# Main.net
KiCad netlist of a schematic drawn in Altium Designer
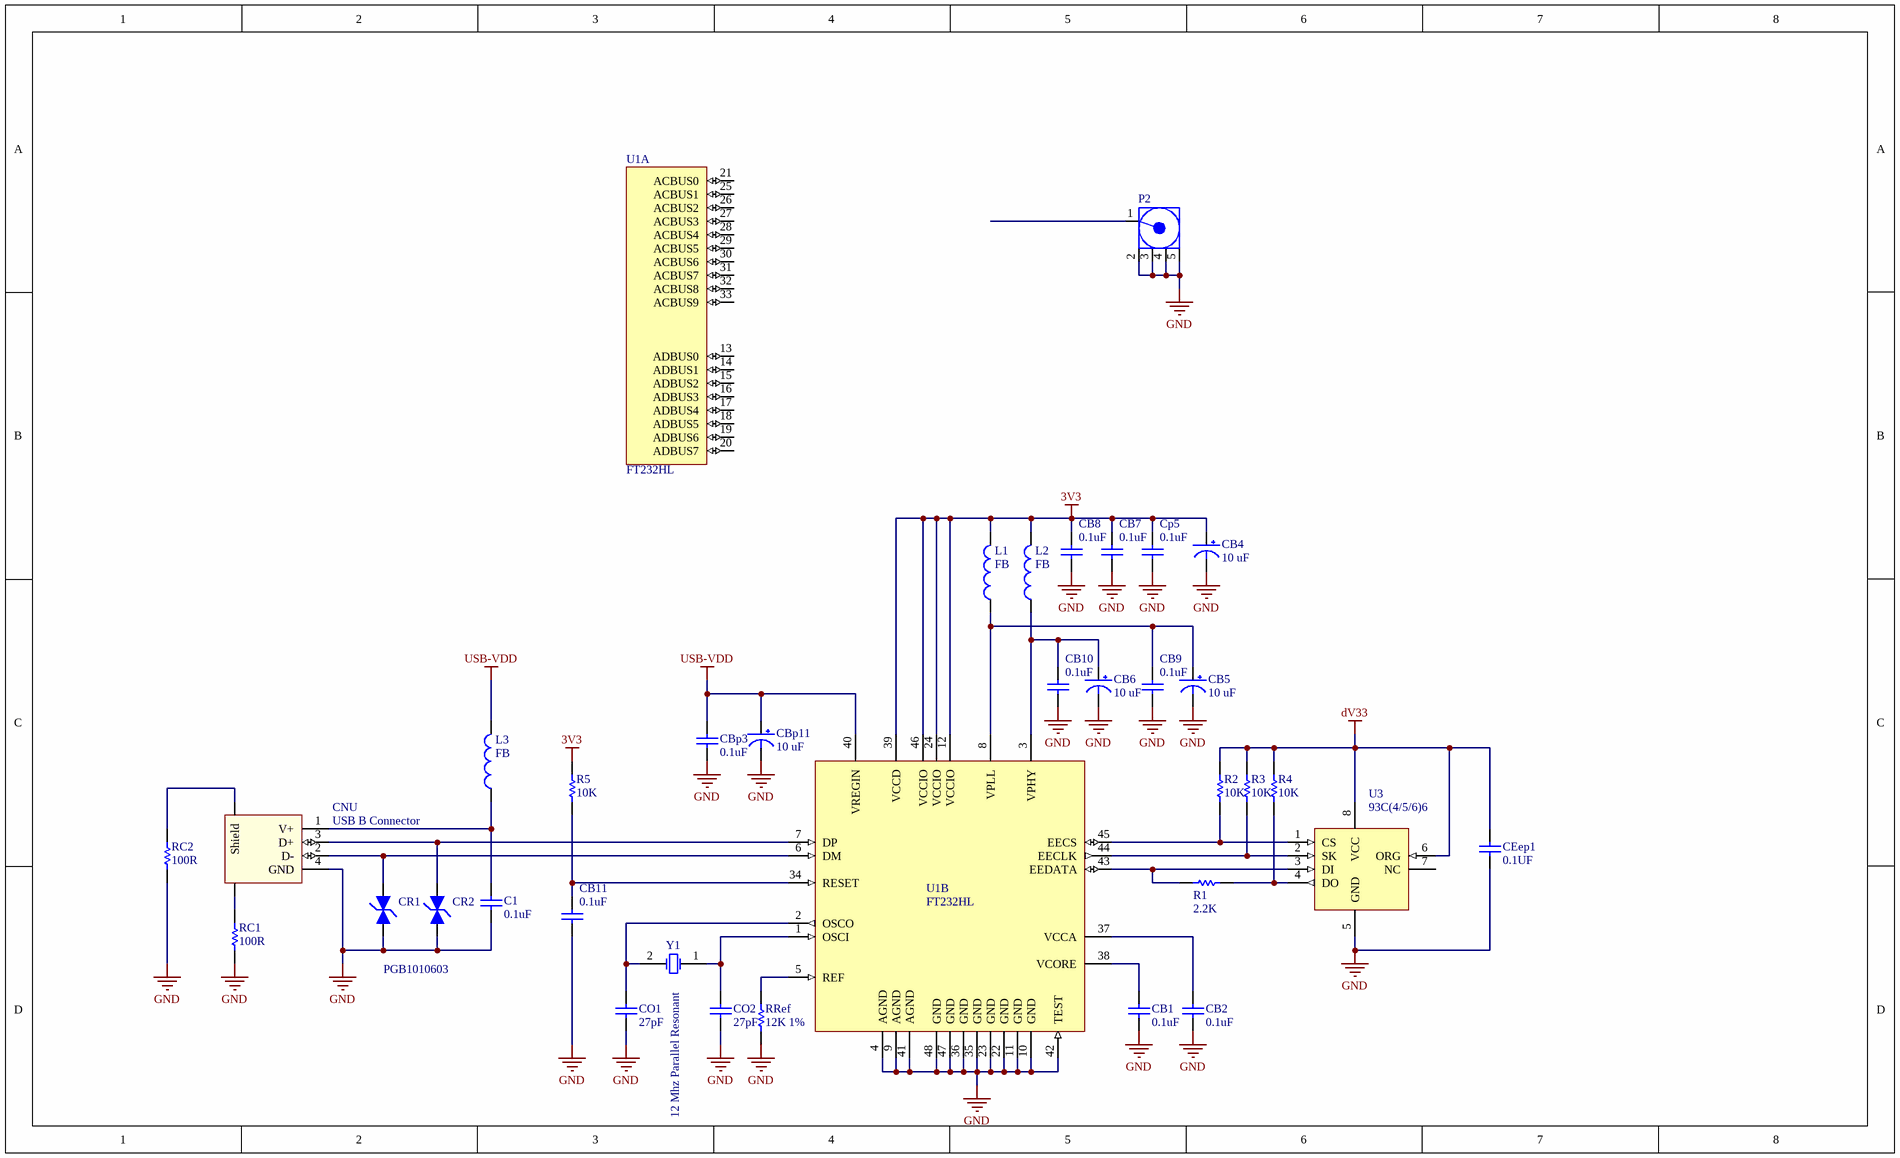
[diagram p0: Main.SchDoc]

(export (version "E")
  (design (tool "Eeschema 10.0.6"))
  (components
    (comp (ref "C1")
      (value "0.1uF")
      (footprint "0805C")
      (description "Capacitor (Semiconductor SIM Model)")
      (fields (field (name "Comment") "Cap Semi") (field (name "PUBLISHER") "Altium Limited"))
      (libsource (lib "Miscellaneous Devices") (part "Cap Semi"))
    )
    (comp (ref "CB1")
      (value "0.1uF")
      (footprint "0603C")
      (description "Capacitor (Semiconductor SIM Model)")
      (fields (field (name "Comment") "Cap Semi") (field (name "PUBLISHER") "Altium Limited"))
      (libsource (lib "Miscellaneous Devices") (part "Cap Semi"))
    )
    (comp (ref "CB2")
      (value "0.1uF")
      (footprint "0603C")
      (description "Capacitor (Semiconductor SIM Model)")
      (fields (field (name "Comment") "Cap Semi") (field (name "PUBLISHER") "Altium Limited"))
      (libsource (lib "Miscellaneous Devices") (part "Cap Semi"))
    )
    (comp (ref "CB4")
      (value "10 uF")
      (footprint "B")
      (libsource (lib "DAQ Sstem") (part "100 uf SMT Panasonic Cap"))
    )
    (comp (ref "CB5")
      (value "10 uF")
      (footprint "B")
      (libsource (lib "DAQ Sstem") (part "100 uf SMT Panasonic Cap"))
    )
    (comp (ref "CB6")
      (value "10 uF")
      (footprint "B")
      (libsource (lib "DAQ Sstem") (part "100 uf SMT Panasonic Cap"))
    )
    (comp (ref "CB7")
      (value "0.1uF")
      (footprint "0603C")
      (description "Capacitor (Semiconductor SIM Model)")
      (fields (field (name "Comment") "Cap Semi") (field (name "PUBLISHER") "Altium Limited"))
      (libsource (lib "Miscellaneous Devices") (part "Cap Semi"))
    )
    (comp (ref "CB8")
      (value "0.1uF")
      (footprint "0603C")
      (description "Capacitor (Semiconductor SIM Model)")
      (fields (field (name "Comment") "Cap Semi") (field (name "PUBLISHER") "Altium Limited"))
      (libsource (lib "Miscellaneous Devices") (part "Cap Semi"))
    )
    (comp (ref "CB9")
      (value "0.1uF")
      (footprint "0603C")
      (description "Capacitor (Semiconductor SIM Model)")
      (fields (field (name "Comment") "Cap Semi") (field (name "PUBLISHER") "Altium Limited"))
      (libsource (lib "Miscellaneous Devices") (part "Cap Semi"))
    )
    (comp (ref "CB10")
      (value "0.1uF")
      (footprint "0603C")
      (description "Capacitor (Semiconductor SIM Model)")
      (fields (field (name "Comment") "Cap Semi") (field (name "PUBLISHER") "Altium Limited"))
      (libsource (lib "Miscellaneous Devices") (part "Cap Semi"))
    )
    (comp (ref "CB11")
      (value "0.1uF")
      (footprint "0603C")
      (description "Capacitor (Semiconductor SIM Model)")
      (fields (field (name "Comment") "Cap Semi") (field (name "PUBLISHER") "Altium Limited"))
      (libsource (lib "Miscellaneous Devices") (part "Cap Semi"))
    )
    (comp (ref "CBp3")
      (value "0.1uF")
      (footprint "0603C")
      (description "Capacitor (Semiconductor SIM Model)")
      (fields (field (name "Comment") "Cap Semi") (field (name "PUBLISHER") "Altium Limited"))
      (libsource (lib "Miscellaneous Devices") (part "Cap Semi"))
    )
    (comp (ref "CBp11")
      (value "10 uF")
      (footprint "B")
      (libsource (lib "DAQ Sstem") (part "100 uf SMT Panasonic Cap"))
    )
    (comp (ref "CEep1")
      (value "0.1UF")
      (footprint "0805C")
      (description "Capacitor (Semiconductor SIM Model)")
      (fields (field (name "Comment") "Cap Semi") (field (name "PUBLISHER") "Altium Limited"))
      (libsource (lib "Miscellaneous Devices") (part "Cap Semi"))
    )
    (comp (ref "CNU")
      (value "USB B Connector")
      (footprint "USB Connector (type B)")
      (libsource (lib "DAQ Sstem") (part "USB B connector - Through hole"))
    )
    (comp (ref "CO1")
      (value "27pF")
      (footprint "0805C")
      (description "Capacitor (Semiconductor SIM Model)")
      (fields (field (name "Comment") "Cap Semi") (field (name "PUBLISHER") "Altium Limited"))
      (libsource (lib "Miscellaneous Devices") (part "Cap Semi"))
    )
    (comp (ref "CO2")
      (value "27pF")
      (footprint "0805C")
      (description "Capacitor (Semiconductor SIM Model)")
      (fields (field (name "Comment") "Cap Semi") (field (name "PUBLISHER") "Altium Limited"))
      (libsource (lib "Miscellaneous Devices") (part "Cap Semi"))
    )
    (comp (ref "Cp5")
      (value "0.1uF")
      (footprint "0603C")
      (description "Capacitor (Semiconductor SIM Model)")
      (fields (field (name "Comment") "Cap Semi") (field (name "PUBLISHER") "Altium Limited"))
      (libsource (lib "Miscellaneous Devices") (part "Cap Semi"))
    )
    (comp (ref "CR1")
      (value "PGB1010603")
      (footprint "0603PG")
      (description "PulseGuard® Lead-Free 0603 Surface Mount Polymeric ESD Suppressors")
      (libsource (lib "DAQ System") (part "PGB1010603"))
    )
    (comp (ref "CR2")
      (value "PGB1010603")
      (footprint "0603PG")
      (description "PulseGuard® Lead-Free 0603 Surface Mount Polymeric ESD Suppressors")
      (libsource (lib "DAQ System") (part "PGB1010603"))
    )
    (comp (ref "L1")
      (value "FB")
      (footprint "1206F")
      (description "Inductor")
      (fields (field (name "PUBLISHER") "Altium Limited"))
      (libsource (lib "Miscellaneous Devices") (part "Inductor"))
    )
    (comp (ref "L2")
      (value "FB")
      (footprint "1206F")
      (description "Inductor")
      (fields (field (name "PUBLISHER") "Altium Limited"))
      (libsource (lib "Miscellaneous Devices") (part "Inductor"))
    )
    (comp (ref "L3")
      (value "FB")
      (footprint "1206F")
      (description "Inductor")
      (fields (field (name "PUBLISHER") "Altium Limited"))
      (libsource (lib "Miscellaneous Devices") (part "Inductor"))
    )
    (comp (ref "P2")
      (value "COAX-M")
      (footprint "SMA Jack - PCB Edge - MultiSize")
      (description "RF Coaxial PCB Connector, MMCX; Thru-Hole, Vertical Mount Plug,  50 Ohm Impedance")
      (fields (field (name "PUBLISHER") "Altium Limited"))
      (libsource (lib "Miscellaneous Connectors") (part "COAX-M"))
    )
    (comp (ref "R1")
      (value "2.2K")
      (footprint "0603R")
      (description "Semiconductor Resistor")
      (fields (field (name "Comment") "Res Semi") (field (name "PUBLISHER") "Altium Limited"))
      (libsource (lib "Miscellaneous Devices") (part "Res Semi"))
    )
    (comp (ref "R2")
      (value "10K")
      (footprint "0603R")
      (description "Semiconductor Resistor")
      (fields (field (name "Comment") "Res Semi") (field (name "PUBLISHER") "Altium Limited"))
      (libsource (lib "Miscellaneous Devices") (part "Res Semi"))
    )
    (comp (ref "R3")
      (value "10K")
      (footprint "0603R")
      (description "Semiconductor Resistor")
      (fields (field (name "Comment") "Res Semi") (field (name "PUBLISHER") "Altium Limited"))
      (libsource (lib "Miscellaneous Devices") (part "Res Semi"))
    )
    (comp (ref "R4")
      (value "10K")
      (footprint "0603R")
      (description "Semiconductor Resistor")
      (fields (field (name "Comment") "Res Semi") (field (name "PUBLISHER") "Altium Limited"))
      (libsource (lib "Miscellaneous Devices") (part "Res Semi"))
    )
    (comp (ref "R5")
      (value "10K")
      (footprint "0805r")
      (description "Semiconductor Resistor")
      (fields (field (name "Comment") "Res Semi") (field (name "PUBLISHER") "Altium Limited"))
      (libsource (lib "Miscellaneous Devices") (part "Res Semi"))
    )
    (comp (ref "RC1")
      (value "100R")
      (footprint "1206R")
      (description "Semiconductor Resistor")
      (fields (field (name "Comment") "Res Semi") (field (name "PUBLISHER") "Altium Limited"))
      (libsource (lib "Miscellaneous Devices") (part "Res Semi"))
    )
    (comp (ref "RC2")
      (value "100R")
      (footprint "1206R")
      (description "Semiconductor Resistor")
      (fields (field (name "Comment") "Res Semi") (field (name "PUBLISHER") "Altium Limited"))
      (libsource (lib "Miscellaneous Devices") (part "Res Semi"))
    )
    (comp (ref "RRef")
      (value "12K 1%")
      (footprint "1206R")
      (description "Semiconductor Resistor")
      (fields (field (name "Comment") "Res Semi") (field (name "PUBLISHER") "Altium Limited"))
      (libsource (lib "Miscellaneous Devices") (part "Res Semi"))
    )
    (comp (ref "U1")
      (value "FT232HL")
      (footprint "TSQFP50P900X900-48N")
      (description "Hi-Speed Single Channel USB UART/FIFO IC")
      (libsource (lib "ICs") (part "FT232HL"))
    )
    (comp (ref "U3")
      (value "93C(4/5/6)6")
      (footprint "SOIC127P600-8CN")
      (description "1/2/4K 3-Wire Serial EEPROM")
      (libsource (lib "DAQ System") (part "93C(4/5/6)6"))
    )
    (comp (ref "Y1")
      (value "12 Mhz Parallel Resonant")
      (footprint "HC-49")
      (description "Crystal Oscillator")
      (fields (field (name "PUBLISHER") "Altium Limited"))
      (libsource (lib "ECS Crystal Oscillator") (part "ECS-10-13-1"))
    )
  )
  (nets
    (net (code "1") (name "3V3") (class "Default")
      (node (ref "CB4") (pin "1") (pinfunction "1_1") (pintype "passive"))
      (node (ref "CB7") (pin "1") (pinfunction "1_1") (pintype "passive"))
      (node (ref "CB8") (pin "1") (pinfunction "1_1") (pintype "passive"))
      (node (ref "Cp5") (pin "1") (pinfunction "1_1") (pintype "passive"))
      (node (ref "L1") (pin "2") (pinfunction "2_2") (pintype "passive"))
      (node (ref "L2") (pin "2") (pinfunction "2_2") (pintype "passive"))
      (node (ref "R5") (pin "1") (pinfunction "1_1") (pintype "passive"))
      (node (ref "U1") (pin "12") (pinfunction "VCCIO_12") (pintype "power_in"))
      (node (ref "U1") (pin "24") (pinfunction "VCCIO_24") (pintype "power_in"))
      (node (ref "U1") (pin "39") (pinfunction "VCCD_39") (pintype "power_in"))
      (node (ref "U1") (pin "46") (pinfunction "VCCIO_46") (pintype "power_in"))
    )
    (net (code "2") (name "GND") (class "Default")
      (node (ref "C1") (pin "1") (pinfunction "1_1") (pintype "passive"))
      (node (ref "CB1") (pin "2") (pinfunction "2_2") (pintype "passive"))
      (node (ref "CB10") (pin "2") (pinfunction "2_2") (pintype "passive"))
      (node (ref "CB11") (pin "2") (pinfunction "2_2") (pintype "passive"))
      (node (ref "CB2") (pin "2") (pinfunction "2_2") (pintype "passive"))
      (node (ref "CB4") (pin "2") (pinfunction "2_2") (pintype "passive"))
      (node (ref "CB5") (pin "2") (pinfunction "2_2") (pintype "passive"))
      (node (ref "CB6") (pin "2") (pinfunction "2_2") (pintype "passive"))
      (node (ref "CB7") (pin "2") (pinfunction "2_2") (pintype "passive"))
      (node (ref "CB8") (pin "2") (pinfunction "2_2") (pintype "passive"))
      (node (ref "CB9") (pin "2") (pinfunction "2_2") (pintype "passive"))
      (node (ref "CBp11") (pin "2") (pinfunction "2_2") (pintype "passive"))
      (node (ref "CBp3") (pin "2") (pinfunction "2_2") (pintype "passive"))
      (node (ref "CEep1") (pin "2") (pinfunction "2_2") (pintype "passive"))
      (node (ref "CNU") (pin "4") (pinfunction "GND_4") (pintype "power_in"))
      (node (ref "CO1") (pin "2") (pinfunction "2_2") (pintype "passive"))
      (node (ref "CO2") (pin "2") (pinfunction "2_2") (pintype "passive"))
      (node (ref "CR1") (pin "2") (pinfunction "2_2") (pintype "passive"))
      (node (ref "CR2") (pin "2") (pinfunction "2_2") (pintype "passive"))
      (node (ref "Cp5") (pin "2") (pinfunction "2_2") (pintype "passive"))
      (node (ref "P2") (pin "2") (pinfunction "GND_2") (pintype "power_in"))
      (node (ref "P2") (pin "3") (pinfunction "GND_3") (pintype "power_in"))
      (node (ref "P2") (pin "4") (pinfunction "GND_4") (pintype "power_in"))
      (node (ref "P2") (pin "5") (pinfunction "GND_5") (pintype "power_in"))
      (node (ref "RC1") (pin "1") (pinfunction "1_1") (pintype "passive"))
      (node (ref "RC2") (pin "1") (pinfunction "1_1") (pintype "passive"))
      (node (ref "RRef") (pin "1") (pinfunction "1_1") (pintype "passive"))
      (node (ref "U1") (pin "10") (pinfunction "GND_10") (pintype "power_in"))
      (node (ref "U1") (pin "11") (pinfunction "GND_11") (pintype "power_in"))
      (node (ref "U1") (pin "22") (pinfunction "GND_22") (pintype "power_in"))
      (node (ref "U1") (pin "23") (pinfunction "GND_23") (pintype "power_in"))
      (node (ref "U1") (pin "35") (pinfunction "GND_35") (pintype "power_in"))
      (node (ref "U1") (pin "36") (pinfunction "GND_36") (pintype "power_in"))
      (node (ref "U1") (pin "4") (pinfunction "AGND_4") (pintype "power_in"))
      (node (ref "U1") (pin "41") (pinfunction "AGND_41") (pintype "power_in"))
      (node (ref "U1") (pin "42") (pinfunction "TEST_42") (pintype "input"))
      (node (ref "U1") (pin "47") (pinfunction "GND_47") (pintype "power_in"))
      (node (ref "U1") (pin "48") (pinfunction "GND_48") (pintype "power_in"))
      (node (ref "U1") (pin "9") (pinfunction "AGND_9") (pintype "power_in"))
      (node (ref "U3") (pin "5") (pinfunction "GND_5") (pintype "power_in"))
    )
    (net (code "3") (name "Net-(CNU-D+)") (class "Default")
      (node (ref "CNU") (pin "3") (pinfunction "D+_3") (pintype "bidirectional"))
      (node (ref "CR2") (pin "1") (pinfunction "1_1") (pintype "passive"))
      (node (ref "U1") (pin "7") (pinfunction "DP_7") (pintype "input"))
    )
    (net (code "4") (name "Net-(CNU-D-)") (class "Default")
      (node (ref "CNU") (pin "2") (pinfunction "D-_2") (pintype "bidirectional"))
      (node (ref "CR1") (pin "1") (pinfunction "1_1") (pintype "passive"))
      (node (ref "U1") (pin "6") (pinfunction "DM_6") (pintype "input"))
    )
    (net (code "5") (name "Net-(CNU-Gnd)") (class "Default")
      (node (ref "CNU") (pin "5") (pinfunction "Gnd_5") (pintype "passive"))
      (node (ref "RC1") (pin "2") (pinfunction "2_2") (pintype "passive"))
    )
    (net (code "6") (name "Net-(CNU-Shield)") (class "Default")
      (node (ref "CNU") (pin "6") (pinfunction "Shield_6") (pintype "passive"))
      (node (ref "RC2") (pin "2") (pinfunction "2_2") (pintype "passive"))
    )
    (net (code "7") (name "Net-(CNU-V+)") (class "Default")
      (node (ref "C1") (pin "2") (pinfunction "2_2") (pintype "passive"))
      (node (ref "CNU") (pin "1") (pinfunction "V+_1") (pintype "power_in"))
      (node (ref "L3") (pin "1") (pinfunction "1_1") (pintype "passive"))
    )
    (net (code "8") (name "Net-(U1B-EECLK)") (class "Default")
      (node (ref "R3") (pin "2") (pinfunction "2_2") (pintype "passive"))
      (node (ref "U1") (pin "44") (pinfunction "EECLK_44") (pintype "output"))
      (node (ref "U3") (pin "2") (pinfunction "SK_2") (pintype "input"))
    )
    (net (code "9") (name "Net-(U1B-EECS)") (class "Default")
      (node (ref "R2") (pin "2") (pinfunction "2_2") (pintype "passive"))
      (node (ref "U1") (pin "45") (pinfunction "EECS_45") (pintype "bidirectional"))
      (node (ref "U3") (pin "1") (pinfunction "CS_1") (pintype "input"))
    )
    (net (code "10") (name "Net-(U1B-EEDATA)") (class "Default")
      (node (ref "R1") (pin "2") (pinfunction "2_2") (pintype "passive"))
      (node (ref "U1") (pin "43") (pinfunction "EEDATA_43") (pintype "bidirectional"))
      (node (ref "U3") (pin "3") (pinfunction "DI_3") (pintype "input"))
    )
    (net (code "11") (name "Net-(U1B-OSCI)") (class "Default")
      (node (ref "CO2") (pin "1") (pinfunction "1_1") (pintype "passive"))
      (node (ref "U1") (pin "1") (pinfunction "OSCI_1") (pintype "input"))
      (node (ref "Y1") (pin "1") (pinfunction "OSC1_1") (pintype "passive"))
    )
    (net (code "12") (name "Net-(U1B-OSCO)") (class "Default")
      (node (ref "CO1") (pin "1") (pinfunction "1_1") (pintype "passive"))
      (node (ref "U1") (pin "2") (pinfunction "OSCO_2") (pintype "output"))
      (node (ref "Y1") (pin "2") (pinfunction "OSC2_2") (pintype "passive"))
    )
    (net (code "13") (name "Net-(U1B-REF)") (class "Default")
      (node (ref "RRef") (pin "2") (pinfunction "2_2") (pintype "passive"))
      (node (ref "U1") (pin "5") (pinfunction "REF_5") (pintype "input"))
    )
    (net (code "14") (name "Net-(U1B-RESET)") (class "Default")
      (node (ref "CB11") (pin "1") (pinfunction "1_1") (pintype "passive"))
      (node (ref "R5") (pin "2") (pinfunction "2_2") (pintype "passive"))
      (node (ref "U1") (pin "34") (pinfunction "RESET_34") (pintype "input"))
    )
    (net (code "15") (name "Net-(U1B-VCCA)") (class "Default")
      (node (ref "CB2") (pin "1") (pinfunction "1_1") (pintype "passive"))
      (node (ref "U1") (pin "37") (pinfunction "VCCA_37") (pintype "power_in"))
    )
    (net (code "16") (name "Net-(U1B-VCORE)") (class "Default")
      (node (ref "CB1") (pin "1") (pinfunction "1_1") (pintype "passive"))
      (node (ref "U1") (pin "38") (pinfunction "VCORE_38") (pintype "power_in"))
    )
    (net (code "17") (name "Net-(U1B-VPHY)") (class "Default")
      (node (ref "CB10") (pin "1") (pinfunction "1_1") (pintype "passive"))
      (node (ref "CB6") (pin "1") (pinfunction "1_1") (pintype "passive"))
      (node (ref "L2") (pin "1") (pinfunction "1_1") (pintype "passive"))
      (node (ref "U1") (pin "3") (pinfunction "VPHY_3") (pintype "power_in"))
    )
    (net (code "18") (name "Net-(U1B-VPLL)") (class "Default")
      (node (ref "CB5") (pin "1") (pinfunction "1_1") (pintype "passive"))
      (node (ref "CB9") (pin "1") (pinfunction "1_1") (pintype "passive"))
      (node (ref "L1") (pin "1") (pinfunction "1_1") (pintype "passive"))
      (node (ref "U1") (pin "8") (pinfunction "VPLL_8") (pintype "power_in"))
    )
    (net (code "19") (name "Net-(U3-DO)") (class "Default")
      (node (ref "R1") (pin "1") (pinfunction "1_1") (pintype "passive"))
      (node (ref "R4") (pin "2") (pinfunction "2_2") (pintype "passive"))
      (node (ref "U3") (pin "4") (pinfunction "DO_4") (pintype "output"))
    )
    (net (code "20") (name "USB-VDD") (class "Default")
      (node (ref "CBp11") (pin "1") (pinfunction "1_1") (pintype "passive"))
      (node (ref "CBp3") (pin "1") (pinfunction "1_1") (pintype "passive"))
      (node (ref "L3") (pin "2") (pinfunction "2_2") (pintype "passive"))
      (node (ref "U1") (pin "40") (pinfunction "VREGIN_40") (pintype "power_in"))
    )
    (net (code "21") (name "dV33") (class "Default")
      (node (ref "CEep1") (pin "1") (pinfunction "1_1") (pintype "passive"))
      (node (ref "R2") (pin "1") (pinfunction "1_1") (pintype "passive"))
      (node (ref "R3") (pin "1") (pinfunction "1_1") (pintype "passive"))
      (node (ref "R4") (pin "1") (pinfunction "1_1") (pintype "passive"))
      (node (ref "U3") (pin "6") (pinfunction "ORG_6") (pintype "input"))
      (node (ref "U3") (pin "8") (pinfunction "VCC_8") (pintype "power_in"))
    )
    (net (code "22") (name "unconnected-(P2-Signal-Pad1)") (class "Default")
      (node (ref "P2") (pin "1") (pinfunction "Signal_1") (pintype "passive"))
    )
    (net (code "23") (name "unconnected-(U1A-ACBUS0-Pad21)") (class "Default")
      (node (ref "U1") (pin "21") (pinfunction "ACBUS0_21") (pintype "bidirectional"))
    )
    (net (code "24") (name "unconnected-(U1A-ACBUS1-Pad25)") (class "Default")
      (node (ref "U1") (pin "25") (pinfunction "ACBUS1_25") (pintype "bidirectional"))
    )
    (net (code "25") (name "unconnected-(U1A-ACBUS2-Pad26)") (class "Default")
      (node (ref "U1") (pin "26") (pinfunction "ACBUS2_26") (pintype "bidirectional"))
    )
    (net (code "26") (name "unconnected-(U1A-ACBUS3-Pad27)") (class "Default")
      (node (ref "U1") (pin "27") (pinfunction "ACBUS3_27") (pintype "bidirectional"))
    )
    (net (code "27") (name "unconnected-(U1A-ACBUS4-Pad28)") (class "Default")
      (node (ref "U1") (pin "28") (pinfunction "ACBUS4_28") (pintype "bidirectional"))
    )
    (net (code "28") (name "unconnected-(U1A-ACBUS5-Pad29)") (class "Default")
      (node (ref "U1") (pin "29") (pinfunction "ACBUS5_29") (pintype "bidirectional"))
    )
    (net (code "29") (name "unconnected-(U1A-ACBUS6-Pad30)") (class "Default")
      (node (ref "U1") (pin "30") (pinfunction "ACBUS6_30") (pintype "bidirectional"))
    )
    (net (code "30") (name "unconnected-(U1A-ACBUS7-Pad31)") (class "Default")
      (node (ref "U1") (pin "31") (pinfunction "ACBUS7_31") (pintype "bidirectional"))
    )
    (net (code "31") (name "unconnected-(U1A-ACBUS8-Pad32)") (class "Default")
      (node (ref "U1") (pin "32") (pinfunction "ACBUS8_32") (pintype "bidirectional"))
    )
    (net (code "32") (name "unconnected-(U1A-ACBUS9-Pad33)") (class "Default")
      (node (ref "U1") (pin "33") (pinfunction "ACBUS9_33") (pintype "bidirectional"))
    )
    (net (code "33") (name "unconnected-(U1A-ADBUS0-Pad13)") (class "Default")
      (node (ref "U1") (pin "13") (pinfunction "ADBUS0_13") (pintype "bidirectional"))
    )
    (net (code "34") (name "unconnected-(U1A-ADBUS1-Pad14)") (class "Default")
      (node (ref "U1") (pin "14") (pinfunction "ADBUS1_14") (pintype "bidirectional"))
    )
    (net (code "35") (name "unconnected-(U1A-ADBUS2-Pad15)") (class "Default")
      (node (ref "U1") (pin "15") (pinfunction "ADBUS2_15") (pintype "bidirectional"))
    )
    (net (code "36") (name "unconnected-(U1A-ADBUS3-Pad16)") (class "Default")
      (node (ref "U1") (pin "16") (pinfunction "ADBUS3_16") (pintype "bidirectional"))
    )
    (net (code "37") (name "unconnected-(U1A-ADBUS4-Pad17)") (class "Default")
      (node (ref "U1") (pin "17") (pinfunction "ADBUS4_17") (pintype "bidirectional"))
    )
    (net (code "38") (name "unconnected-(U1A-ADBUS5-Pad18)") (class "Default")
      (node (ref "U1") (pin "18") (pinfunction "ADBUS5_18") (pintype "bidirectional"))
    )
    (net (code "39") (name "unconnected-(U1A-ADBUS6-Pad19)") (class "Default")
      (node (ref "U1") (pin "19") (pinfunction "ADBUS6_19") (pintype "bidirectional"))
    )
    (net (code "40") (name "unconnected-(U1A-ADBUS7-Pad20)") (class "Default")
      (node (ref "U1") (pin "20") (pinfunction "ADBUS7_20") (pintype "bidirectional"))
    )
    (net (code "41") (name "unconnected-(U3-NC-Pad7)") (class "Default")
      (node (ref "U3") (pin "7") (pinfunction "NC_7") (pintype "passive"))
    )
  )
)
